# WyLight_v6.net
KiCad netlist of a schematic drawn in EAGLE
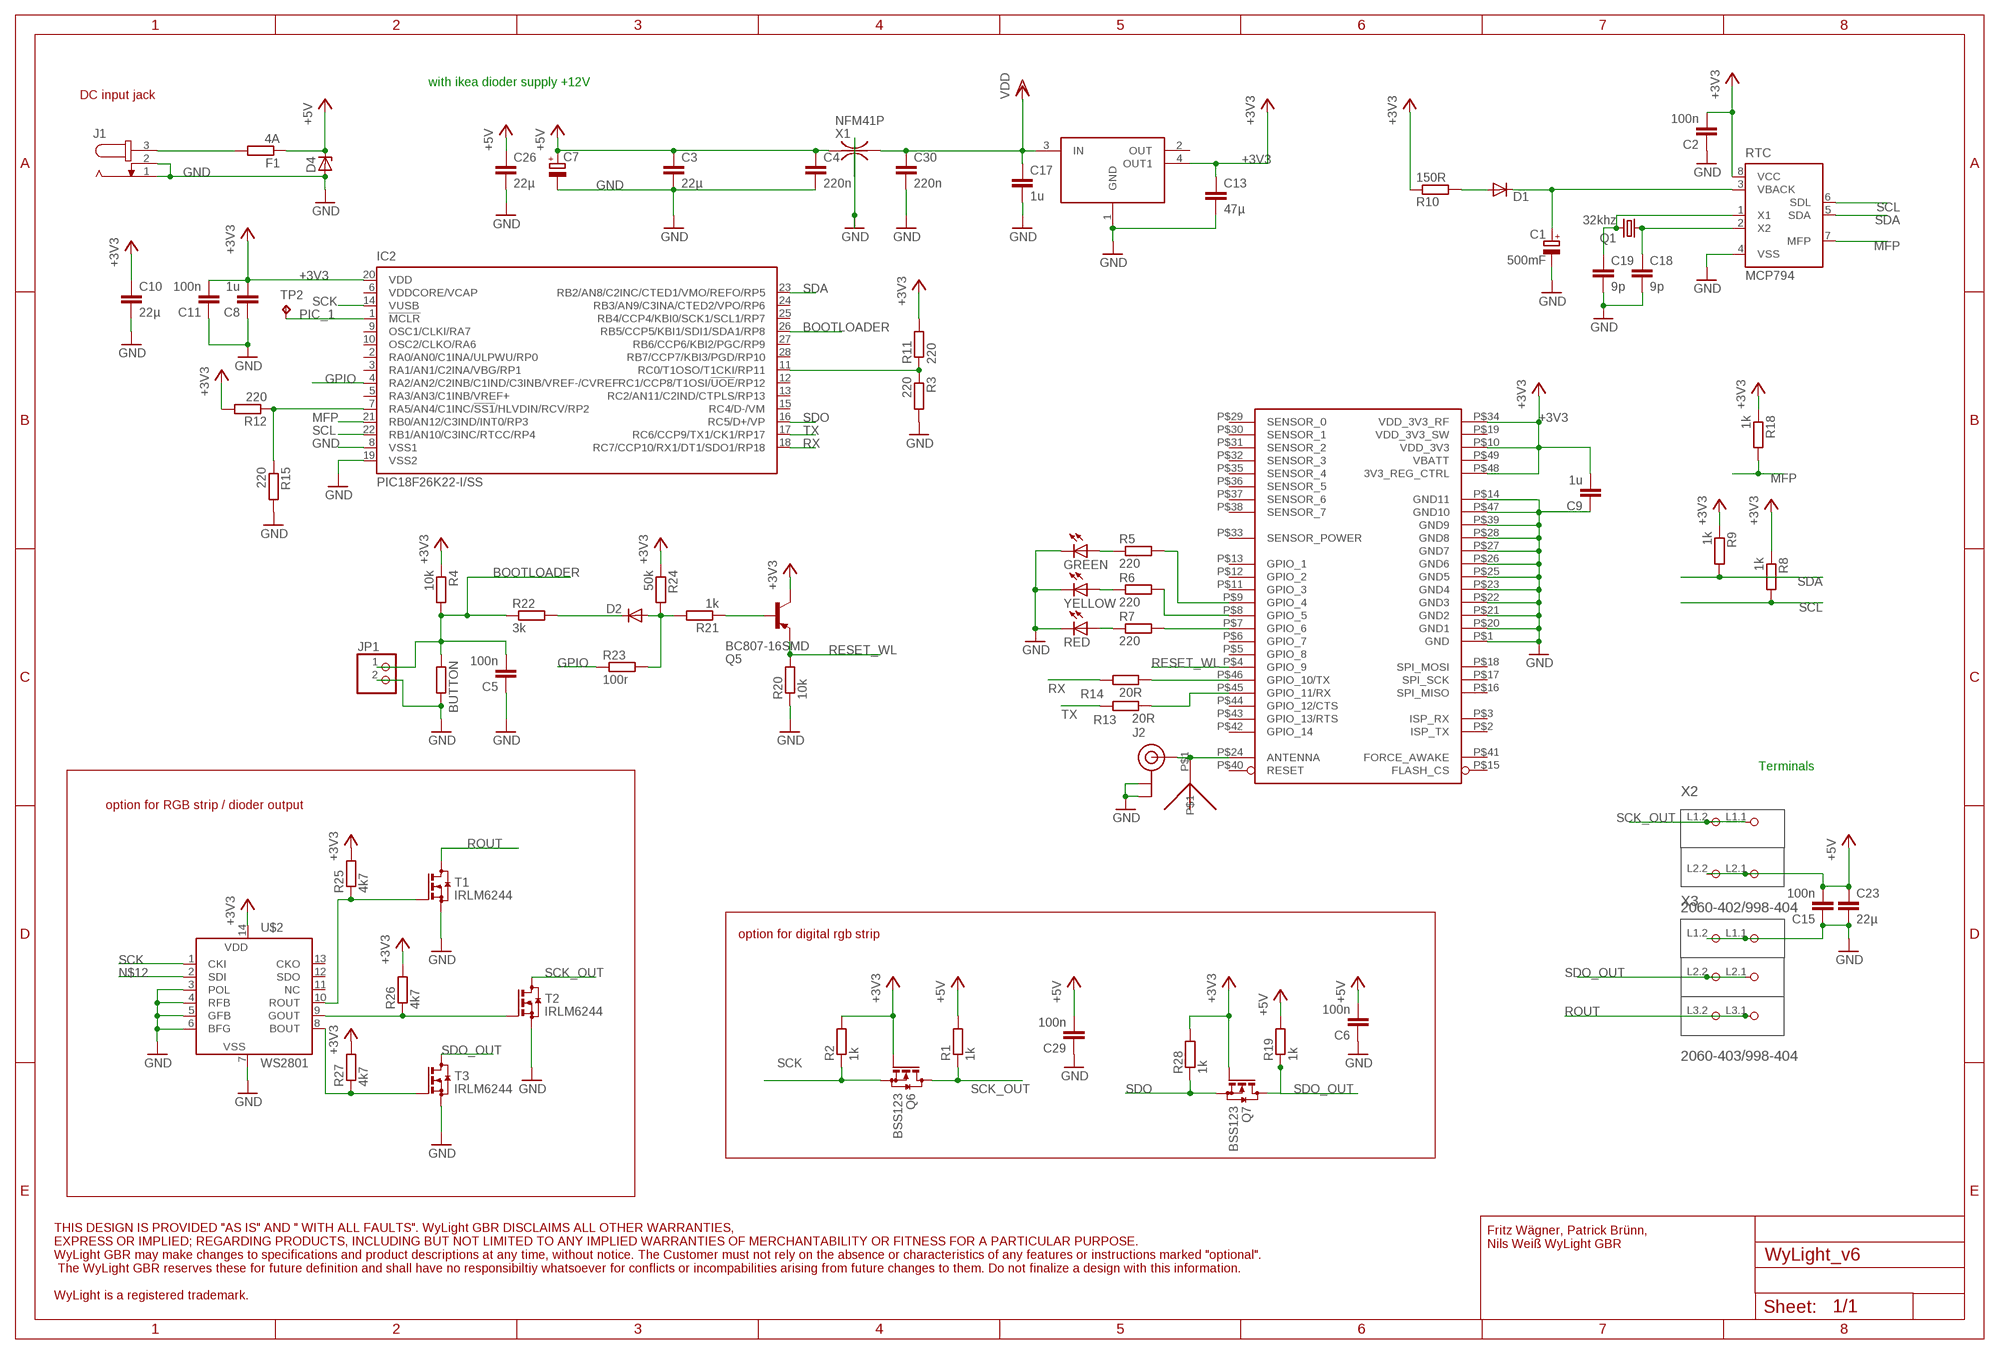
[diagram p0: schematic, sheet 1]

(export (version "E")
  (design (tool "Eeschema 10.0.6"))
  (components
    (comp (ref "BUTTON")
      (value "R-EU_M2309")
      (footprint "eagle-import:M2309")
      (libsource (lib "eagle-import") (part "R-EU_M2309"))
    )
    (comp (ref "C1")
      (value "500mF")
      (footprint "eagle-import:E5-10,5")
      (libsource (lib "eagle-import") (part "CPOL-EUE5-10.5"))
    )
    (comp (ref "C2")
      (value "100n")
      (footprint "eagle-import:C0603K")
      (libsource (lib "eagle-import") (part "C-EUC0603K"))
    )
    (comp (ref "C3")
      (value "22µ")
      (footprint "eagle-import:C1210")
      (libsource (lib "eagle-import") (part "C-EUC1210"))
    )
    (comp (ref "C4")
      (value "220n")
      (footprint "eagle-import:C0603")
      (libsource (lib "eagle-import") (part "C-EUC0603"))
    )
    (comp (ref "C5")
      (value "100n")
      (footprint "eagle-import:C0603K")
      (libsource (lib "eagle-import") (part "C-EUC0603K"))
    )
    (comp (ref "C6")
      (value "100n")
      (footprint "eagle-import:C0603K")
      (libsource (lib "eagle-import") (part "C-EUC0603K"))
    )
    (comp (ref "C7")
      (value "CPOL-EUC/6032-28R")
      (footprint "eagle-import:C_6032-28R")
      (libsource (lib "eagle-import") (part "CPOL-EUC/6032-28R"))
    )
    (comp (ref "C8")
      (value "1u")
      (footprint "eagle-import:C0603")
      (libsource (lib "eagle-import") (part "C-EUC0603"))
    )
    (comp (ref "C9")
      (value "1u")
      (footprint "eagle-import:C0603")
      (libsource (lib "eagle-import") (part "C-EUC0603"))
    )
    (comp (ref "C10")
      (value "22µ")
      (footprint "eagle-import:C1210")
      (libsource (lib "eagle-import") (part "C-EUC1210"))
    )
    (comp (ref "C11")
      (value "100n")
      (footprint "eagle-import:C0603")
      (libsource (lib "eagle-import") (part "C-EUC0603"))
    )
    (comp (ref "C13")
      (value "47µ")
      (footprint "eagle-import:C1210")
      (libsource (lib "eagle-import") (part "C-EUC1210"))
    )
    (comp (ref "C15")
      (value "100n")
      (footprint "eagle-import:C0603")
      (libsource (lib "eagle-import") (part "C-EUC0603"))
    )
    (comp (ref "C17")
      (value "1u")
      (footprint "eagle-import:C0603")
      (libsource (lib "eagle-import") (part "C-EUC0603"))
    )
    (comp (ref "C18")
      (value "9p")
      (footprint "eagle-import:C0603")
      (libsource (lib "eagle-import") (part "C-EUC0603"))
    )
    (comp (ref "C19")
      (value "9p")
      (footprint "eagle-import:C0603")
      (libsource (lib "eagle-import") (part "C-EUC0603"))
    )
    (comp (ref "C23")
      (value "22µ")
      (footprint "eagle-import:C1210")
      (libsource (lib "eagle-import") (part "C-EUC1210"))
    )
    (comp (ref "C26")
      (value "22µ")
      (footprint "eagle-import:C1210")
      (libsource (lib "eagle-import") (part "C-EUC1210"))
    )
    (comp (ref "C29")
      (value "100n")
      (footprint "eagle-import:C0603K")
      (libsource (lib "eagle-import") (part "C-EUC0603K"))
    )
    (comp (ref "C30")
      (value "220n")
      (footprint "eagle-import:C0603")
      (libsource (lib "eagle-import") (part "C-EUC0603"))
    )
    (comp (ref "D1")
      (value "DIODE-SOD323-W")
      (footprint "eagle-import:SOD323-W")
      (libsource (lib "eagle-import") (part "DIODE-SOD323-W"))
    )
    (comp (ref "D2")
      (value "DIODE-SOD323-W")
      (footprint "eagle-import:SOD323-W")
      (libsource (lib "eagle-import") (part "DIODE-SOD323-W"))
    )
    (comp (ref "D4")
      (value "ZENER-DIODESMB")
      (footprint "eagle-import:SMB")
      (libsource (lib "eagle-import") (part "ZENER-DIODESMB"))
    )
    (comp (ref "F1")
      (value "4A")
      (footprint "eagle-import:M2309")
      (libsource (lib "eagle-import") (part "R-EU_M2309"))
    )
    (comp (ref "GREEN")
      (value "LEDCHIPLED_0603")
      (footprint "eagle-import:CHIPLED_0603")
      (libsource (lib "eagle-import") (part "LEDCHIPLED_0603"))
    )
    (comp (ref "IC2")
      (value "PIC18F26K22-I/SS")
      (footprint "eagle-import:SSOP28")
      (libsource (lib "eagle-import") (part "PIC18F2J53SS7"))
    )
    (comp (ref "J1")
      (value "JACK-PLUG0")
      (footprint "eagle-import:SPC4077")
      (libsource (lib "eagle-import") (part "JACK-PLUG0"))
    )
    (comp (ref "J2")
      (value "U.FL")
      (footprint "eagle-import:U.FL")
      (libsource (lib "eagle-import") (part "U.FL"))
    )
    (comp (ref "JP1")
      (value "PINHD-1X2_2.00")
      (footprint "eagle-import:1X02M")
      (libsource (lib "eagle-import") (part "PINHD-1X2_2.00"))
    )
    (comp (ref "Q1")
      (value "32khz")
      (footprint "eagle-import:Q_SMD_32_1,5")
      (libsource (lib "eagle-import") (part "Q_SMD_32_15"))
    )
    (comp (ref "Q5")
      (value "BC807-16SMD")
      (footprint "eagle-import:SOT23-BEC")
      (libsource (lib "eagle-import") (part "BC807SMD-16"))
    )
    (comp (ref "Q6")
      (value "BSS123")
      (footprint "eagle-import:SOT23")
      (libsource (lib "eagle-import") (part "BSS123"))
    )
    (comp (ref "Q7")
      (value "BSS123")
      (footprint "eagle-import:SOT23")
      (libsource (lib "eagle-import") (part "BSS123"))
    )
    (comp (ref "R1")
      (value "1k")
      (footprint "eagle-import:R0603")
      (libsource (lib "eagle-import") (part "R-EU_R0603"))
    )
    (comp (ref "R2")
      (value "1k")
      (footprint "eagle-import:R0603")
      (libsource (lib "eagle-import") (part "R-EU_R0603"))
    )
    (comp (ref "R3")
      (value "220")
      (footprint "eagle-import:R0603")
      (libsource (lib "eagle-import") (part "R-EU_R0603"))
    )
    (comp (ref "R4")
      (value "10k")
      (footprint "eagle-import:R0603")
      (libsource (lib "eagle-import") (part "R-EU_R0603"))
    )
    (comp (ref "R5")
      (value "220")
      (footprint "eagle-import:R0603")
      (libsource (lib "eagle-import") (part "R-EU_R0603"))
    )
    (comp (ref "R6")
      (value "220")
      (footprint "eagle-import:R0603")
      (libsource (lib "eagle-import") (part "R-EU_R0603"))
    )
    (comp (ref "R7")
      (value "220")
      (footprint "eagle-import:R0603")
      (libsource (lib "eagle-import") (part "R-EU_R0603"))
    )
    (comp (ref "R8")
      (value "1k")
      (footprint "eagle-import:R0603")
      (libsource (lib "eagle-import") (part "R-EU_R0603"))
    )
    (comp (ref "R9")
      (value "1k")
      (footprint "eagle-import:R0603")
      (libsource (lib "eagle-import") (part "R-EU_R0603"))
    )
    (comp (ref "R10")
      (value "150R")
      (footprint "eagle-import:R0603")
      (libsource (lib "eagle-import") (part "R-EU_R0603"))
    )
    (comp (ref "R11")
      (value "220")
      (footprint "eagle-import:R0603")
      (libsource (lib "eagle-import") (part "R-EU_R0603"))
    )
    (comp (ref "R12")
      (value "220")
      (footprint "eagle-import:R0603")
      (libsource (lib "eagle-import") (part "R-EU_R0603"))
    )
    (comp (ref "R13")
      (value "20R")
      (footprint "eagle-import:R0603")
      (libsource (lib "eagle-import") (part "R-EU_R0603"))
    )
    (comp (ref "R14")
      (value "20R")
      (footprint "eagle-import:R0603")
      (libsource (lib "eagle-import") (part "R-EU_R0603"))
    )
    (comp (ref "R15")
      (value "220")
      (footprint "eagle-import:R0603")
      (libsource (lib "eagle-import") (part "R-EU_R0603"))
    )
    (comp (ref "R18")
      (value "1k")
      (footprint "eagle-import:R0603")
      (libsource (lib "eagle-import") (part "R-EU_R0603"))
    )
    (comp (ref "R19")
      (value "1k")
      (footprint "eagle-import:R0603")
      (libsource (lib "eagle-import") (part "R-EU_R0603"))
    )
    (comp (ref "R20")
      (value "10k")
      (footprint "eagle-import:R0603")
      (libsource (lib "eagle-import") (part "R-EU_R0603"))
    )
    (comp (ref "R21")
      (value "1k")
      (footprint "eagle-import:R0603")
      (libsource (lib "eagle-import") (part "R-EU_R0603"))
    )
    (comp (ref "R22")
      (value "3k")
      (footprint "eagle-import:R0603")
      (libsource (lib "eagle-import") (part "R-EU_R0603"))
    )
    (comp (ref "R23")
      (value "100r")
      (footprint "eagle-import:R0603")
      (libsource (lib "eagle-import") (part "R-EU_R0603"))
    )
    (comp (ref "R24")
      (value "50k")
      (footprint "eagle-import:R0603")
      (libsource (lib "eagle-import") (part "R-EU_R0603"))
    )
    (comp (ref "R25")
      (value "4k7")
      (footprint "eagle-import:R0603")
      (libsource (lib "eagle-import") (part "R-EU_R0603"))
    )
    (comp (ref "R26")
      (value "4k7")
      (footprint "eagle-import:R0603")
      (libsource (lib "eagle-import") (part "R-EU_R0603"))
    )
    (comp (ref "R27")
      (value "4k7")
      (footprint "eagle-import:R0603")
      (libsource (lib "eagle-import") (part "R-EU_R0603"))
    )
    (comp (ref "R28")
      (value "1k")
      (footprint "eagle-import:R0603")
      (libsource (lib "eagle-import") (part "R-EU_R0603"))
    )
    (comp (ref "RED")
      (value "LEDCHIPLED_0603")
      (footprint "eagle-import:CHIPLED_0603")
      (libsource (lib "eagle-import") (part "LEDCHIPLED_0603"))
    )
    (comp (ref "RTC")
      (value "MCP794")
      (footprint "eagle-import:SO-08")
      (libsource (lib "eagle-import") (part "MCP794"))
    )
    (comp (ref "T1")
      (value "IRLM6244")
      (footprint "eagle-import:SOT23")
      (libsource (lib "eagle-import") (part "IRLM6244"))
    )
    (comp (ref "T2")
      (value "IRLM6244")
      (footprint "eagle-import:SOT23")
      (libsource (lib "eagle-import") (part "IRLM6244"))
    )
    (comp (ref "T3")
      (value "IRLM6244")
      (footprint "eagle-import:SOT23")
      (libsource (lib "eagle-import") (part "IRLM6244"))
    )
    (comp (ref "TP2")
      (value "TPB1,27")
      (footprint "eagle-import:B1,27")
      (libsource (lib "eagle-import") (part "TPB1,27"))
    )
    (comp (ref "U$1")
      (value "RN171")
      (footprint "eagle-import:WLAN_MOD_HAND")
      (libsource (lib "eagle-import") (part "RN-171"))
    )
    (comp (ref "U$2")
      (value "WS2801")
      (footprint "eagle-import:SO14")
      (libsource (lib "eagle-import") (part "WS2801"))
    )
    (comp (ref "U$3")
      (value "WE-MCAWE-MCA")
      (footprint "eagle-import:WE-MCA")
      (libsource (lib "eagle-import") (part "WE-MCAWE-MCA"))
    )
    (comp (ref "U2")
      (value "TLV1117")
      (footprint "eagle-import:SOT223")
      (libsource (lib "eagle-import") (part "TLV1117"))
    )
    (comp (ref "X1")
      (value "NFM41P")
      (footprint "eagle-import:NFM41P")
      (libsource (lib "eagle-import") (part "NFM41P"))
    )
    (comp (ref "X2")
      (value "2060-402/998-404")
      (footprint "eagle-import:P-2060-402_998-404")
      (libsource (lib "eagle-import") (part "2060-402/998-404"))
    )
    (comp (ref "X3")
      (value "2060-403/998-404")
      (footprint "eagle-import:P-2060-403_998-404")
      (libsource (lib "eagle-import") (part "2060-403/998-404"))
    )
    (comp (ref "YELLOW")
      (value "LEDCHIPLED_0603")
      (footprint "eagle-import:CHIPLED_0603")
      (libsource (lib "eagle-import") (part "LEDCHIPLED_0603"))
    )
  )
  (nets
    (net (code "1") (name "+3V3") (class "Default")
      (node (ref "C10") (pin "1") (pinfunction "1_1") (pintype "passive"))
      (node (ref "C11") (pin "2") (pinfunction "2_2") (pintype "passive"))
      (node (ref "C13") (pin "1") (pinfunction "1_1") (pintype "passive"))
      (node (ref "C2") (pin "2") (pinfunction "2_2") (pintype "passive"))
      (node (ref "C8") (pin "2") (pinfunction "2_2") (pintype "passive"))
      (node (ref "C9") (pin "2") (pinfunction "2_2") (pintype "passive"))
      (node (ref "IC2") (pin "20") (pinfunction "VDD_20") (pintype "input"))
      (node (ref "Q5") (pin "C") (pinfunction "C_C") (pintype "passive"))
      (node (ref "Q6") (pin "1") (pinfunction "G_1") (pintype "passive"))
      (node (ref "Q7") (pin "1") (pinfunction "G_1") (pintype "passive"))
      (node (ref "R10") (pin "1") (pinfunction "1_1") (pintype "passive"))
      (node (ref "R11") (pin "2") (pinfunction "2_2") (pintype "passive"))
      (node (ref "R12") (pin "2") (pinfunction "2_2") (pintype "passive"))
      (node (ref "R18") (pin "1") (pinfunction "1_1") (pintype "passive"))
      (node (ref "R2") (pin "2") (pinfunction "2_2") (pintype "passive"))
      (node (ref "R24") (pin "1") (pinfunction "1_1") (pintype "passive"))
      (node (ref "R25") (pin "2") (pinfunction "2_2") (pintype "passive"))
      (node (ref "R26") (pin "2") (pinfunction "2_2") (pintype "passive"))
      (node (ref "R27") (pin "2") (pinfunction "2_2") (pintype "passive"))
      (node (ref "R28") (pin "2") (pinfunction "2_2") (pintype "passive"))
      (node (ref "R4") (pin "1") (pinfunction "1_1") (pintype "passive"))
      (node (ref "R8") (pin "1") (pinfunction "1_1") (pintype "passive"))
      (node (ref "R9") (pin "1") (pinfunction "1_1") (pintype "passive"))
      (node (ref "RTC") (pin "8") (pinfunction "VCC_8") (pintype "power_in"))
      (node (ref "U$1") (pin "P$10") (pinfunction "VDD_3V3_P$10") (pintype "bidirectional"))
      (node (ref "U$1") (pin "P$34") (pinfunction "VDD_3V3_RF_P$34") (pintype "bidirectional"))
      (node (ref "U$1") (pin "P$48") (pinfunction "3V3_REG_CTRL_P$48") (pintype "bidirectional"))
      (node (ref "U$2") (pin "14") (pinfunction "VCC_14") (pintype "power_in"))
      (node (ref "U2") (pin "4") (pinfunction "OUT1_4") (pintype "bidirectional"))
    )
    (net (code "2") (name "+5V") (class "Default")
      (node (ref "C15") (pin "2") (pinfunction "2_2") (pintype "passive"))
      (node (ref "C23") (pin "1") (pinfunction "1_1") (pintype "passive"))
      (node (ref "C26") (pin "1") (pinfunction "1_1") (pintype "passive"))
      (node (ref "C29") (pin "2") (pinfunction "2_2") (pintype "passive"))
      (node (ref "C3") (pin "1") (pinfunction "1_1") (pintype "passive"))
      (node (ref "C4") (pin "1") (pinfunction "1_1") (pintype "passive"))
      (node (ref "C6") (pin "2") (pinfunction "2_2") (pintype "passive"))
      (node (ref "C7") (pin "+") (pinfunction "+_+") (pintype "passive"))
      (node (ref "D4") (pin "C") (pinfunction "C_C") (pintype "passive"))
      (node (ref "F1") (pin "1") (pinfunction "1_1") (pintype "passive"))
      (node (ref "R1") (pin "2") (pinfunction "2_2") (pintype "passive"))
      (node (ref "R19") (pin "2") (pinfunction "2_2") (pintype "passive"))
      (node (ref "X1") (pin "1") (pinfunction "1_1") (pintype "passive"))
      (node (ref "X2") (pin "L2.1") (pinfunction "P2.1_L2.1") (pintype "bidirectional"))
      (node (ref "X2") (pin "L2.2") (pinfunction "P2.2_L2.2") (pintype "bidirectional"))
    )
    (net (code "3") (name "/BOOTLOADER") (class "Default")
      (node (ref "BUTTON") (pin "1") (pinfunction "1_1") (pintype "passive"))
      (node (ref "C5") (pin "2") (pinfunction "2_2") (pintype "passive"))
      (node (ref "IC2") (pin "26") (pinfunction "RB5/CCP5/KBI1/SDI1/SDA1/RP8_26") (pintype "bidirectional"))
      (node (ref "JP1") (pin "1") (pinfunction "1_1") (pintype "passive"))
      (node (ref "R22") (pin "1") (pinfunction "1_1") (pintype "passive"))
      (node (ref "R4") (pin "2") (pinfunction "2_2") (pintype "passive"))
    )
    (net (code "4") (name "/GPIO") (class "Default")
      (node (ref "IC2") (pin "4") (pinfunction "RA2/AN2/C2INB/C1IND/C3INB/VREF-/CVREF_4") (pintype "bidirectional"))
      (node (ref "R23") (pin "1") (pinfunction "1_1") (pintype "passive"))
    )
    (net (code "5") (name "/MFP") (class "Default")
      (node (ref "IC2") (pin "21") (pinfunction "RB0/AN12/C3IND/INT0/RP3_21") (pintype "bidirectional"))
      (node (ref "R18") (pin "2") (pinfunction "2_2") (pintype "passive"))
      (node (ref "RTC") (pin "7") (pinfunction "MFP_7") (pintype "output"))
    )
    (net (code "6") (name "/N$12") (class "Default")
      (node (ref "U$2") (pin "2") (pinfunction "SDI_2") (pintype "bidirectional"))
    )
    (net (code "7") (name "/PIC_1") (class "Default")
      (node (ref "IC2") (pin "1") (pinfunction "~{MCLR}_1") (pintype "input"))
      (node (ref "TP2") (pin "TP") (pinfunction "TP_TP") (pintype "input"))
    )
    (net (code "8") (name "/RESET_WL") (class "Default")
      (node (ref "Q5") (pin "E") (pinfunction "E_E") (pintype "passive"))
      (node (ref "R20") (pin "2") (pinfunction "2_2") (pintype "passive"))
      (node (ref "U$1") (pin "P$4") (pinfunction "GPIO_9_P$4") (pintype "bidirectional"))
    )
    (net (code "9") (name "/ROUT") (class "Default")
      (node (ref "T1") (pin "3") (pinfunction "D_3") (pintype "passive"))
      (node (ref "X3") (pin "L3.1") (pinfunction "P3.1_L3.1") (pintype "bidirectional"))
      (node (ref "X3") (pin "L3.2") (pinfunction "P3.2_L3.2") (pintype "bidirectional"))
    )
    (net (code "10") (name "/RX") (class "Default")
      (node (ref "IC2") (pin "18") (pinfunction "RC7/CCP10/RX1/DT1/SDO1/RP18_18") (pintype "bidirectional"))
      (node (ref "R14") (pin "1") (pinfunction "1_1") (pintype "passive"))
    )
    (net (code "11") (name "/SCK") (class "Default")
      (node (ref "IC2") (pin "14") (pinfunction "VUSB_14") (pintype "input"))
      (node (ref "Q6") (pin "2") (pinfunction "S_2") (pintype "passive"))
      (node (ref "R2") (pin "1") (pinfunction "1_1") (pintype "passive"))
      (node (ref "U$2") (pin "1") (pinfunction "CKI_1") (pintype "input"))
    )
    (net (code "12") (name "/SCK_OUT") (class "Default")
      (node (ref "Q6") (pin "3") (pinfunction "D_3") (pintype "passive"))
      (node (ref "R1") (pin "1") (pinfunction "1_1") (pintype "passive"))
      (node (ref "T2") (pin "3") (pinfunction "D_3") (pintype "passive"))
      (node (ref "X2") (pin "L1.1") (pinfunction "P1.1_L1.1") (pintype "bidirectional"))
      (node (ref "X2") (pin "L1.2") (pinfunction "P1.2_L1.2") (pintype "bidirectional"))
    )
    (net (code "13") (name "/SCL") (class "Default")
      (node (ref "IC2") (pin "22") (pinfunction "RB1/AN10/C3INC/RTCC/RP4_22") (pintype "bidirectional"))
      (node (ref "R8") (pin "2") (pinfunction "2_2") (pintype "passive"))
      (node (ref "RTC") (pin "6") (pinfunction "SDL_6") (pintype "input"))
    )
    (net (code "14") (name "/SDA") (class "Default")
      (node (ref "IC2") (pin "23") (pinfunction "RB2/AN8/C2INC/CTED1/VMO/REFO/RP5_23") (pintype "bidirectional"))
      (node (ref "R9") (pin "2") (pinfunction "2_2") (pintype "passive"))
      (node (ref "RTC") (pin "5") (pinfunction "SDA_5") (pintype "bidirectional"))
    )
    (net (code "15") (name "/SDO") (class "Default")
      (node (ref "IC2") (pin "16") (pinfunction "RC5/D+/VP_16") (pintype "bidirectional"))
      (node (ref "Q7") (pin "2") (pinfunction "S_2") (pintype "passive"))
      (node (ref "R28") (pin "1") (pinfunction "1_1") (pintype "passive"))
    )
    (net (code "16") (name "/SDO_OUT") (class "Default")
      (node (ref "Q7") (pin "3") (pinfunction "D_3") (pintype "passive"))
      (node (ref "R19") (pin "1") (pinfunction "1_1") (pintype "passive"))
      (node (ref "T3") (pin "3") (pinfunction "D_3") (pintype "passive"))
      (node (ref "X3") (pin "L2.1") (pinfunction "P2.1_L2.1") (pintype "bidirectional"))
      (node (ref "X3") (pin "L2.2") (pinfunction "P2.2_L2.2") (pintype "bidirectional"))
    )
    (net (code "17") (name "/TX") (class "Default")
      (node (ref "IC2") (pin "17") (pinfunction "RC6/CCP9/TX1/CK1/RP17_17") (pintype "bidirectional"))
      (node (ref "R13") (pin "1") (pinfunction "1_1") (pintype "passive"))
    )
    (net (code "18") (name "GND") (class "Default")
      (node (ref "BUTTON") (pin "2") (pinfunction "2_2") (pintype "passive"))
      (node (ref "C1") (pin "-") (pinfunction "-_-") (pintype "passive"))
      (node (ref "C10") (pin "2") (pinfunction "2_2") (pintype "passive"))
      (node (ref "C11") (pin "1") (pinfunction "1_1") (pintype "passive"))
      (node (ref "C13") (pin "2") (pinfunction "2_2") (pintype "passive"))
      (node (ref "C15") (pin "1") (pinfunction "1_1") (pintype "passive"))
      (node (ref "C17") (pin "2") (pinfunction "2_2") (pintype "passive"))
      (node (ref "C18") (pin "2") (pinfunction "2_2") (pintype "passive"))
      (node (ref "C19") (pin "2") (pinfunction "2_2") (pintype "passive"))
      (node (ref "C2") (pin "1") (pinfunction "1_1") (pintype "passive"))
      (node (ref "C23") (pin "2") (pinfunction "2_2") (pintype "passive"))
      (node (ref "C26") (pin "2") (pinfunction "2_2") (pintype "passive"))
      (node (ref "C29") (pin "1") (pinfunction "1_1") (pintype "passive"))
      (node (ref "C3") (pin "2") (pinfunction "2_2") (pintype "passive"))
      (node (ref "C30") (pin "2") (pinfunction "2_2") (pintype "passive"))
      (node (ref "C4") (pin "2") (pinfunction "2_2") (pintype "passive"))
      (node (ref "C5") (pin "1") (pinfunction "1_1") (pintype "passive"))
      (node (ref "C6") (pin "1") (pinfunction "1_1") (pintype "passive"))
      (node (ref "C7") (pin "-") (pinfunction "-_-") (pintype "passive"))
      (node (ref "C8") (pin "1") (pinfunction "1_1") (pintype "passive"))
      (node (ref "C9") (pin "1") (pinfunction "1_1") (pintype "passive"))
      (node (ref "D4") (pin "A") (pinfunction "A_A") (pintype "passive"))
      (node (ref "GREEN") (pin "C") (pinfunction "C_C") (pintype "passive"))
      (node (ref "IC2") (pin "19") (pinfunction "VSS2_19") (pintype "input"))
      (node (ref "IC2") (pin "8") (pinfunction "VSS1_8") (pintype "input"))
      (node (ref "J1") (pin "1") (pinfunction "1_1") (pintype "passive"))
      (node (ref "J1") (pin "2") (pinfunction "2_2") (pintype "passive"))
      (node (ref "J2") (pin "P$1") (pinfunction "GND_P$1") (pintype "bidirectional"))
      (node (ref "J2") (pin "P$2") (pinfunction "GND_P$2") (pintype "bidirectional"))
      (node (ref "JP1") (pin "2") (pinfunction "2_2") (pintype "passive"))
      (node (ref "R15") (pin "2") (pinfunction "2_2") (pintype "passive"))
      (node (ref "R20") (pin "1") (pinfunction "1_1") (pintype "passive"))
      (node (ref "R3") (pin "2") (pinfunction "2_2") (pintype "passive"))
      (node (ref "RED") (pin "C") (pinfunction "C_C") (pintype "passive"))
      (node (ref "RTC") (pin "4") (pinfunction "VSS_4") (pintype "power_in"))
      (node (ref "T1") (pin "2") (pinfunction "S_2") (pintype "passive"))
      (node (ref "T2") (pin "2") (pinfunction "S_2") (pintype "passive"))
      (node (ref "T3") (pin "2") (pinfunction "S_2") (pintype "passive"))
      (node (ref "U$1") (pin "P$1") (pinfunction "GND_P$1") (pintype "power_in"))
      (node (ref "U$1") (pin "P$14") (pinfunction "GND11_P$14") (pintype "power_in"))
      (node (ref "U$1") (pin "P$20") (pinfunction "GND1_P$20") (pintype "power_in"))
      (node (ref "U$1") (pin "P$21") (pinfunction "GND2_P$21") (pintype "power_in"))
      (node (ref "U$1") (pin "P$22") (pinfunction "GND3_P$22") (pintype "power_in"))
      (node (ref "U$1") (pin "P$23") (pinfunction "GND4_P$23") (pintype "power_in"))
      (node (ref "U$1") (pin "P$25") (pinfunction "GND5_P$25") (pintype "power_in"))
      (node (ref "U$1") (pin "P$26") (pinfunction "GND6_P$26") (pintype "power_in"))
      (node (ref "U$1") (pin "P$27") (pinfunction "GND7_P$27") (pintype "power_in"))
      (node (ref "U$1") (pin "P$28") (pinfunction "GND8_P$28") (pintype "power_in"))
      (node (ref "U$1") (pin "P$39") (pinfunction "GND9_P$39") (pintype "power_in"))
      (node (ref "U$1") (pin "P$47") (pinfunction "GND10_P$47") (pintype "power_in"))
      (node (ref "U$2") (pin "3") (pinfunction "POL_3") (pintype "bidirectional"))
      (node (ref "U$2") (pin "4") (pinfunction "RFB_4") (pintype "bidirectional"))
      (node (ref "U$2") (pin "5") (pinfunction "GFB_5") (pintype "bidirectional"))
      (node (ref "U$2") (pin "6") (pinfunction "BFG_6") (pintype "bidirectional"))
      (node (ref "U$2") (pin "7") (pinfunction "GND_7") (pintype "power_in"))
      (node (ref "U2") (pin "1") (pinfunction "GND_1") (pintype "bidirectional"))
      (node (ref "X1") (pin "2@1") (pinfunction "2_2@1") (pintype "passive"))
      (node (ref "X1") (pin "2@2") (pinfunction "2_2@2") (pintype "passive"))
      (node (ref "X3") (pin "L1.1") (pinfunction "P1.1_L1.1") (pintype "bidirectional"))
      (node (ref "X3") (pin "L1.2") (pinfunction "P1.2_L1.2") (pintype "bidirectional"))
      (node (ref "YELLOW") (pin "C") (pinfunction "C_C") (pintype "passive"))
    )
    (net (code "19") (name "Net-(D1-PadA)") (class "Default")
      (node (ref "D1") (pin "A") (pinfunction "A_A") (pintype "passive"))
      (node (ref "R10") (pin "2") (pinfunction "2_2") (pintype "passive"))
    )
    (net (code "20") (name "Net-(D2-PadA)") (class "Default")
      (node (ref "D2") (pin "A") (pinfunction "A_A") (pintype "passive"))
      (node (ref "R21") (pin "2") (pinfunction "2_2") (pintype "passive"))
      (node (ref "R23") (pin "2") (pinfunction "2_2") (pintype "passive"))
      (node (ref "R24") (pin "2") (pinfunction "2_2") (pintype "passive"))
    )
    (net (code "21") (name "Net-(D2-PadC)") (class "Default")
      (node (ref "D2") (pin "C") (pinfunction "C_C") (pintype "passive"))
      (node (ref "R22") (pin "2") (pinfunction "2_2") (pintype "passive"))
    )
    (net (code "22") (name "Net-(F1-Pad2)") (class "Default")
      (node (ref "F1") (pin "2") (pinfunction "2_2") (pintype "passive"))
      (node (ref "J1") (pin "3") (pinfunction "3_3") (pintype "passive"))
    )
    (net (code "23") (name "Net-(GREEN-PadA)") (class "Default")
      (node (ref "GREEN") (pin "A") (pinfunction "A_A") (pintype "passive"))
      (node (ref "R5") (pin "1") (pinfunction "1_1") (pintype "passive"))
    )
    (net (code "24") (name "Net-(IC2-RA5{slash}AN4{slash}C1INC{slash}~{SS1}{slash}HLVDIN{slash}RCV{slash}RP2)") (class "Default")
      (node (ref "IC2") (pin "7") (pinfunction "RA5/AN4/C1INC/~{SS1}/HLVDIN/RCV/RP2_7") (pintype "bidirectional"))
      (node (ref "R12") (pin "1") (pinfunction "1_1") (pintype "passive"))
      (node (ref "R15") (pin "1") (pinfunction "1_1") (pintype "passive"))
    )
    (net (code "25") (name "Net-(IC2-RC0{slash}T1OSO{slash}T1CKI{slash}RP11)") (class "Default")
      (node (ref "IC2") (pin "11") (pinfunction "RC0/T1OSO/T1CKI/RP11_11") (pintype "bidirectional"))
      (node (ref "R11") (pin "1") (pinfunction "1_1") (pintype "passive"))
      (node (ref "R3") (pin "1") (pinfunction "1_1") (pintype "passive"))
    )
    (net (code "26") (name "Net-(J2-SIGNAL)") (class "Default")
      (node (ref "J2") (pin "P$3") (pinfunction "SIGNAL_P$3") (pintype "bidirectional"))
      (node (ref "U$1") (pin "P$24") (pinfunction "ANTENNA_P$24") (pintype "bidirectional"))
      (node (ref "U$3") (pin "P$1") (pinfunction "P$1_P$1") (pintype "input"))
    )
    (net (code "27") (name "Net-(Q5-PadB)") (class "Default")
      (node (ref "Q5") (pin "B") (pinfunction "B_B") (pintype "passive"))
      (node (ref "R21") (pin "1") (pinfunction "1_1") (pintype "passive"))
    )
    (net (code "28") (name "Net-(R6-Pad1)") (class "Default")
      (node (ref "R6") (pin "1") (pinfunction "1_1") (pintype "passive"))
      (node (ref "YELLOW") (pin "A") (pinfunction "A_A") (pintype "passive"))
    )
    (net (code "29") (name "Net-(R7-Pad1)") (class "Default")
      (node (ref "R7") (pin "1") (pinfunction "1_1") (pintype "passive"))
      (node (ref "RED") (pin "A") (pinfunction "A_A") (pintype "passive"))
    )
    (net (code "30") (name "Net-(RTC-VBACK)") (class "Default")
      (node (ref "C1") (pin "+") (pinfunction "+_+") (pintype "passive"))
      (node (ref "D1") (pin "C") (pinfunction "C_C") (pintype "passive"))
      (node (ref "RTC") (pin "3") (pinfunction "VBACK_3") (pintype "input"))
    )
    (net (code "31") (name "Net-(RTC-X1)") (class "Default")
      (node (ref "C19") (pin "1") (pinfunction "1_1") (pintype "passive"))
      (node (ref "Q1") (pin "2") (pinfunction "2_2") (pintype "passive"))
      (node (ref "RTC") (pin "1") (pinfunction "X1_1") (pintype "input"))
    )
    (net (code "32") (name "Net-(RTC-X2)") (class "Default")
      (node (ref "C18") (pin "1") (pinfunction "1_1") (pintype "passive"))
      (node (ref "Q1") (pin "1") (pinfunction "1_1") (pintype "passive"))
      (node (ref "RTC") (pin "2") (pinfunction "X2_2") (pintype "output"))
    )
    (net (code "33") (name "Net-(T1-G)") (class "Default")
      (node (ref "R25") (pin "1") (pinfunction "1_1") (pintype "passive"))
      (node (ref "T1") (pin "1") (pinfunction "G_1") (pintype "passive"))
      (node (ref "U$2") (pin "10") (pinfunction "ROUT_10") (pintype "bidirectional"))
    )
    (net (code "34") (name "Net-(T2-G)") (class "Default")
      (node (ref "R26") (pin "1") (pinfunction "1_1") (pintype "passive"))
      (node (ref "T2") (pin "1") (pinfunction "G_1") (pintype "passive"))
      (node (ref "U$2") (pin "9") (pinfunction "GOUT_9") (pintype "bidirectional"))
    )
    (net (code "35") (name "Net-(T3-G)") (class "Default")
      (node (ref "R27") (pin "1") (pinfunction "1_1") (pintype "passive"))
      (node (ref "T3") (pin "1") (pinfunction "G_1") (pintype "passive"))
      (node (ref "U$2") (pin "8") (pinfunction "BOUT_8") (pintype "bidirectional"))
    )
    (net (code "36") (name "Net-(U$1-GPIO_4)") (class "Default")
      (node (ref "R5") (pin "2") (pinfunction "2_2") (pintype "passive"))
      (node (ref "U$1") (pin "P$9") (pinfunction "GPIO_4_P$9") (pintype "bidirectional"))
    )
    (net (code "37") (name "Net-(U$1-GPIO_5)") (class "Default")
      (node (ref "R6") (pin "2") (pinfunction "2_2") (pintype "passive"))
      (node (ref "U$1") (pin "P$8") (pinfunction "GPIO_5_P$8") (pintype "bidirectional"))
    )
    (net (code "38") (name "Net-(U$1-GPIO_6)") (class "Default")
      (node (ref "R7") (pin "2") (pinfunction "2_2") (pintype "passive"))
      (node (ref "U$1") (pin "P$7") (pinfunction "GPIO_6_P$7") (pintype "bidirectional"))
    )
    (net (code "39") (name "Net-(U$1-GPIO_10{slash}TX)") (class "Default")
      (node (ref "R14") (pin "2") (pinfunction "2_2") (pintype "passive"))
      (node (ref "U$1") (pin "P$46") (pinfunction "GPIO_10/TX_P$46") (pintype "bidirectional"))
    )
    (net (code "40") (name "Net-(U$1-GPIO_11{slash}RX)") (class "Default")
      (node (ref "R13") (pin "2") (pinfunction "2_2") (pintype "passive"))
      (node (ref "U$1") (pin "P$45") (pinfunction "GPIO_11/RX_P$45") (pintype "bidirectional"))
    )
    (net (code "41") (name "VDD") (class "Default")
      (node (ref "C17") (pin "1") (pinfunction "1_1") (pintype "passive"))
      (node (ref "C30") (pin "1") (pinfunction "1_1") (pintype "passive"))
      (node (ref "U2") (pin "3") (pinfunction "IN_3") (pintype "bidirectional"))
      (node (ref "X1") (pin "3") (pinfunction "3_3") (pintype "passive"))
    )
    (net (code "42") (name "unconnected-(IC2-OSC1{slash}CLKI{slash}RA7-Pad9)") (class "Default")
      (node (ref "IC2") (pin "9") (pinfunction "OSC1/CLKI/RA7_9") (pintype "bidirectional"))
    )
    (net (code "43") (name "unconnected-(IC2-OSC2{slash}CLKO{slash}RA6-Pad10)") (class "Default")
      (node (ref "IC2") (pin "10") (pinfunction "OSC2/CLKO/RA6_10") (pintype "bidirectional"))
    )
    (net (code "44") (name "unconnected-(IC2-RA0{slash}AN0{slash}C1INA{slash}ULPWU{slash}RP0-Pad2)") (class "Default")
      (node (ref "IC2") (pin "2") (pinfunction "RA0/AN0/C1INA/ULPWU/RP0_2") (pintype "bidirectional"))
    )
    (net (code "45") (name "unconnected-(IC2-RA1{slash}AN1{slash}C2INA{slash}VBG{slash}RP1-Pad3)") (class "Default")
      (node (ref "IC2") (pin "3") (pinfunction "RA1/AN1/C2INA/VBG/RP1_3") (pintype "bidirectional"))
    )
    (net (code "46") (name "unconnected-(IC2-RA3{slash}AN3{slash}C1INB{slash}VREF+-Pad5)") (class "Default")
      (node (ref "IC2") (pin "5") (pinfunction "RA3/AN3/C1INB/VREF+_5") (pintype "bidirectional"))
    )
    (net (code "47") (name "unconnected-(IC2-RB3{slash}AN9{slash}C3INA{slash}CTED2{slash}VPO{slash}RP6-Pad24)") (class "Default")
      (node (ref "IC2") (pin "24") (pinfunction "RB3/AN9/C3INA/CTED2/VPO/RP6_24") (pintype "bidirectional"))
    )
    (net (code "48") (name "unconnected-(IC2-RB4{slash}CCP4{slash}KBI0{slash}SCK1{slash}SCL1{slash}RP7-Pad25)") (class "Default")
      (node (ref "IC2") (pin "25") (pinfunction "RB4/CCP4/KBI0/SCK1/SCL1/RP7_25") (pintype "bidirectional"))
    )
    (net (code "49") (name "unconnected-(IC2-RB6{slash}CCP6{slash}KBI2{slash}PGC{slash}RP9-Pad27)") (class "Default")
      (node (ref "IC2") (pin "27") (pinfunction "RB6/CCP6/KBI2/PGC/RP9_27") (pintype "bidirectional"))
    )
    (net (code "50") (name "unconnected-(IC2-RB7{slash}CCP7{slash}KBI3{slash}PGD{slash}RP10-Pad28)") (class "Default")
      (node (ref "IC2") (pin "28") (pinfunction "RB7/CCP7/KBI3/PGD/RP10_28") (pintype "bidirectional"))
    )
    (net (code "51") (name "unconnected-(IC2-RC1{slash}CCP8{slash}T1OSI{slash}~{UOE}{slash}RP12-Pad12)") (class "Default")
      (node (ref "IC2") (pin "12") (pinfunction "RC1/CCP8/T1OSI/~{UOE}/RP12_12") (pintype "bidirectional"))
    )
    (net (code "52") (name "unconnected-(IC2-RC2{slash}AN11{slash}C2IND{slash}CTPLS{slash}RP13-Pad13)") (class "Default")
      (node (ref "IC2") (pin "13") (pinfunction "RC2/AN11/C2IND/CTPLS/RP13_13") (pintype "bidirectional"))
    )
    (net (code "53") (name "unconnected-(IC2-RC4{slash}D-{slash}VM-Pad15)") (class "Default")
      (node (ref "IC2") (pin "15") (pinfunction "RC4/D-/VM_15") (pintype "bidirectional"))
    )
    (net (code "54") (name "unconnected-(IC2-VDDCORE{slash}VCAP-Pad6)") (class "Default")
      (node (ref "IC2") (pin "6") (pinfunction "VDDCORE/VCAP_6") (pintype "input"))
    )
    (net (code "55") (name "unconnected-(U$1-FLASH_CS-PadP$15)") (class "Default")
      (node (ref "U$1") (pin "P$15") (pinfunction "FLASH_CS_P$15") (pintype "bidirectional"))
    )
    (net (code "56") (name "unconnected-(U$1-FORCE_AWAKE-PadP$41)") (class "Default")
      (node (ref "U$1") (pin "P$41") (pinfunction "FORCE_AWAKE_P$41") (pintype "bidirectional"))
    )
    (net (code "57") (name "unconnected-(U$1-GPIO_1-PadP$13)") (class "Default")
      (node (ref "U$1") (pin "P$13") (pinfunction "GPIO_1_P$13") (pintype "bidirectional"))
    )
    (net (code "58") (name "unconnected-(U$1-GPIO_2-PadP$12)") (class "Default")
      (node (ref "U$1") (pin "P$12") (pinfunction "GPIO_2_P$12") (pintype "bidirectional"))
    )
    (net (code "59") (name "unconnected-(U$1-GPIO_3-PadP$11)") (class "Default")
      (node (ref "U$1") (pin "P$11") (pinfunction "GPIO_3_P$11") (pintype "bidirectional"))
    )
    (net (code "60") (name "unconnected-(U$1-GPIO_7-PadP$6)") (class "Default")
      (node (ref "U$1") (pin "P$6") (pinfunction "GPIO_7_P$6") (pintype "bidirectional"))
    )
    (net (code "61") (name "unconnected-(U$1-GPIO_8-PadP$5)") (class "Default")
      (node (ref "U$1") (pin "P$5") (pinfunction "GPIO_8_P$5") (pintype "bidirectional"))
    )
    (net (code "62") (name "unconnected-(U$1-GPIO_12{slash}CTS-PadP$44)") (class "Default")
      (node (ref "U$1") (pin "P$44") (pinfunction "GPIO_12/CTS_P$44") (pintype "bidirectional"))
    )
    (net (code "63") (name "unconnected-(U$1-GPIO_13{slash}RTS-PadP$43)") (class "Default")
      (node (ref "U$1") (pin "P$43") (pinfunction "GPIO_13/RTS_P$43") (pintype "bidirectional"))
    )
    (net (code "64") (name "unconnected-(U$1-GPIO_14-PadP$42)") (class "Default")
      (node (ref "U$1") (pin "P$42") (pinfunction "GPIO_14_P$42") (pintype "bidirectional"))
    )
    (net (code "65") (name "unconnected-(U$1-ISP_RX-PadP$3)") (class "Default")
      (node (ref "U$1") (pin "P$3") (pinfunction "ISP_RX_P$3") (pintype "bidirectional"))
    )
    (net (code "66") (name "unconnected-(U$1-ISP_TX-PadP$2)") (class "Default")
      (node (ref "U$1") (pin "P$2") (pinfunction "ISP_TX_P$2") (pintype "bidirectional"))
    )
    (net (code "67") (name "unconnected-(U$1-RESET-PadP$40)") (class "Default")
      (node (ref "U$1") (pin "P$40") (pinfunction "RESET_P$40") (pintype "bidirectional"))
    )
    (net (code "68") (name "unconnected-(U$1-SENSOR_0-PadP$29)") (class "Default")
      (node (ref "U$1") (pin "P$29") (pinfunction "SENSOR_0_P$29") (pintype "input"))
    )
    (net (code "69") (name "unconnected-(U$1-SENSOR_1-PadP$30)") (class "Default")
      (node (ref "U$1") (pin "P$30") (pinfunction "SENSOR_1_P$30") (pintype "input"))
    )
    (net (code "70") (name "unconnected-(U$1-SENSOR_2-PadP$31)") (class "Default")
      (node (ref "U$1") (pin "P$31") (pinfunction "SENSOR_2_P$31") (pintype "input"))
    )
    (net (code "71") (name "unconnected-(U$1-SENSOR_3-PadP$32)") (class "Default")
      (node (ref "U$1") (pin "P$32") (pinfunction "SENSOR_3_P$32") (pintype "input"))
    )
    (net (code "72") (name "unconnected-(U$1-SENSOR_4-PadP$35)") (class "Default")
      (node (ref "U$1") (pin "P$35") (pinfunction "SENSOR_4_P$35") (pintype "input"))
    )
    (net (code "73") (name "unconnected-(U$1-SENSOR_5-PadP$36)") (class "Default")
      (node (ref "U$1") (pin "P$36") (pinfunction "SENSOR_5_P$36") (pintype "input"))
    )
    (net (code "74") (name "unconnected-(U$1-SENSOR_6-PadP$37)") (class "Default")
      (node (ref "U$1") (pin "P$37") (pinfunction "SENSOR_6_P$37") (pintype "input"))
    )
    (net (code "75") (name "unconnected-(U$1-SENSOR_7-PadP$38)") (class "Default")
      (node (ref "U$1") (pin "P$38") (pinfunction "SENSOR_7_P$38") (pintype "input"))
    )
    (net (code "76") (name "unconnected-(U$1-SENSOR_POWER-PadP$33)") (class "Default")
      (node (ref "U$1") (pin "P$33") (pinfunction "SENSOR_POWER_P$33") (pintype "bidirectional"))
    )
    (net (code "77") (name "unconnected-(U$1-SPI_MISO-PadP$16)") (class "Default")
      (node (ref "U$1") (pin "P$16") (pinfunction "SPI_MISO_P$16") (pintype "bidirectional"))
    )
    (net (code "78") (name "unconnected-(U$1-SPI_MOSI-PadP$18)") (class "Default")
      (node (ref "U$1") (pin "P$18") (pinfunction "SPI_MOSI_P$18") (pintype "bidirectional"))
    )
    (net (code "79") (name "unconnected-(U$1-SPI_SCK-PadP$17)") (class "Default")
      (node (ref "U$1") (pin "P$17") (pinfunction "SPI_SCK_P$17") (pintype "bidirectional"))
    )
    (net (code "80") (name "unconnected-(U$1-VBATT-PadP$49)") (class "Default")
      (node (ref "U$1") (pin "P$49") (pinfunction "VBATT_P$49") (pintype "bidirectional"))
    )
    (net (code "81") (name "unconnected-(U$1-VDD_3V3_SW-PadP$19)") (class "Default")
      (node (ref "U$1") (pin "P$19") (pinfunction "VDD_3V3_SW_P$19") (pintype "bidirectional"))
    )
    (net (code "82") (name "unconnected-(U$2-CKO-Pad13)") (class "Default")
      (node (ref "U$2") (pin "13") (pinfunction "CKO_13") (pintype "bidirectional"))
    )
    (net (code "83") (name "unconnected-(U$2-NC-Pad11)") (class "Default")
      (node (ref "U$2") (pin "11") (pinfunction "NC_11") (pintype "bidirectional"))
    )
    (net (code "84") (name "unconnected-(U$2-SDO-Pad12)") (class "Default")
      (node (ref "U$2") (pin "12") (pinfunction "SDO_12") (pintype "bidirectional"))
    )
    (net (code "85") (name "unconnected-(U2-OUT-Pad2)") (class "Default")
      (node (ref "U2") (pin "2") (pinfunction "OUT_2") (pintype "bidirectional"))
    )
  )
)
